# Startracker_Power.net
KiCad netlist of a schematic drawn in Altium Designer
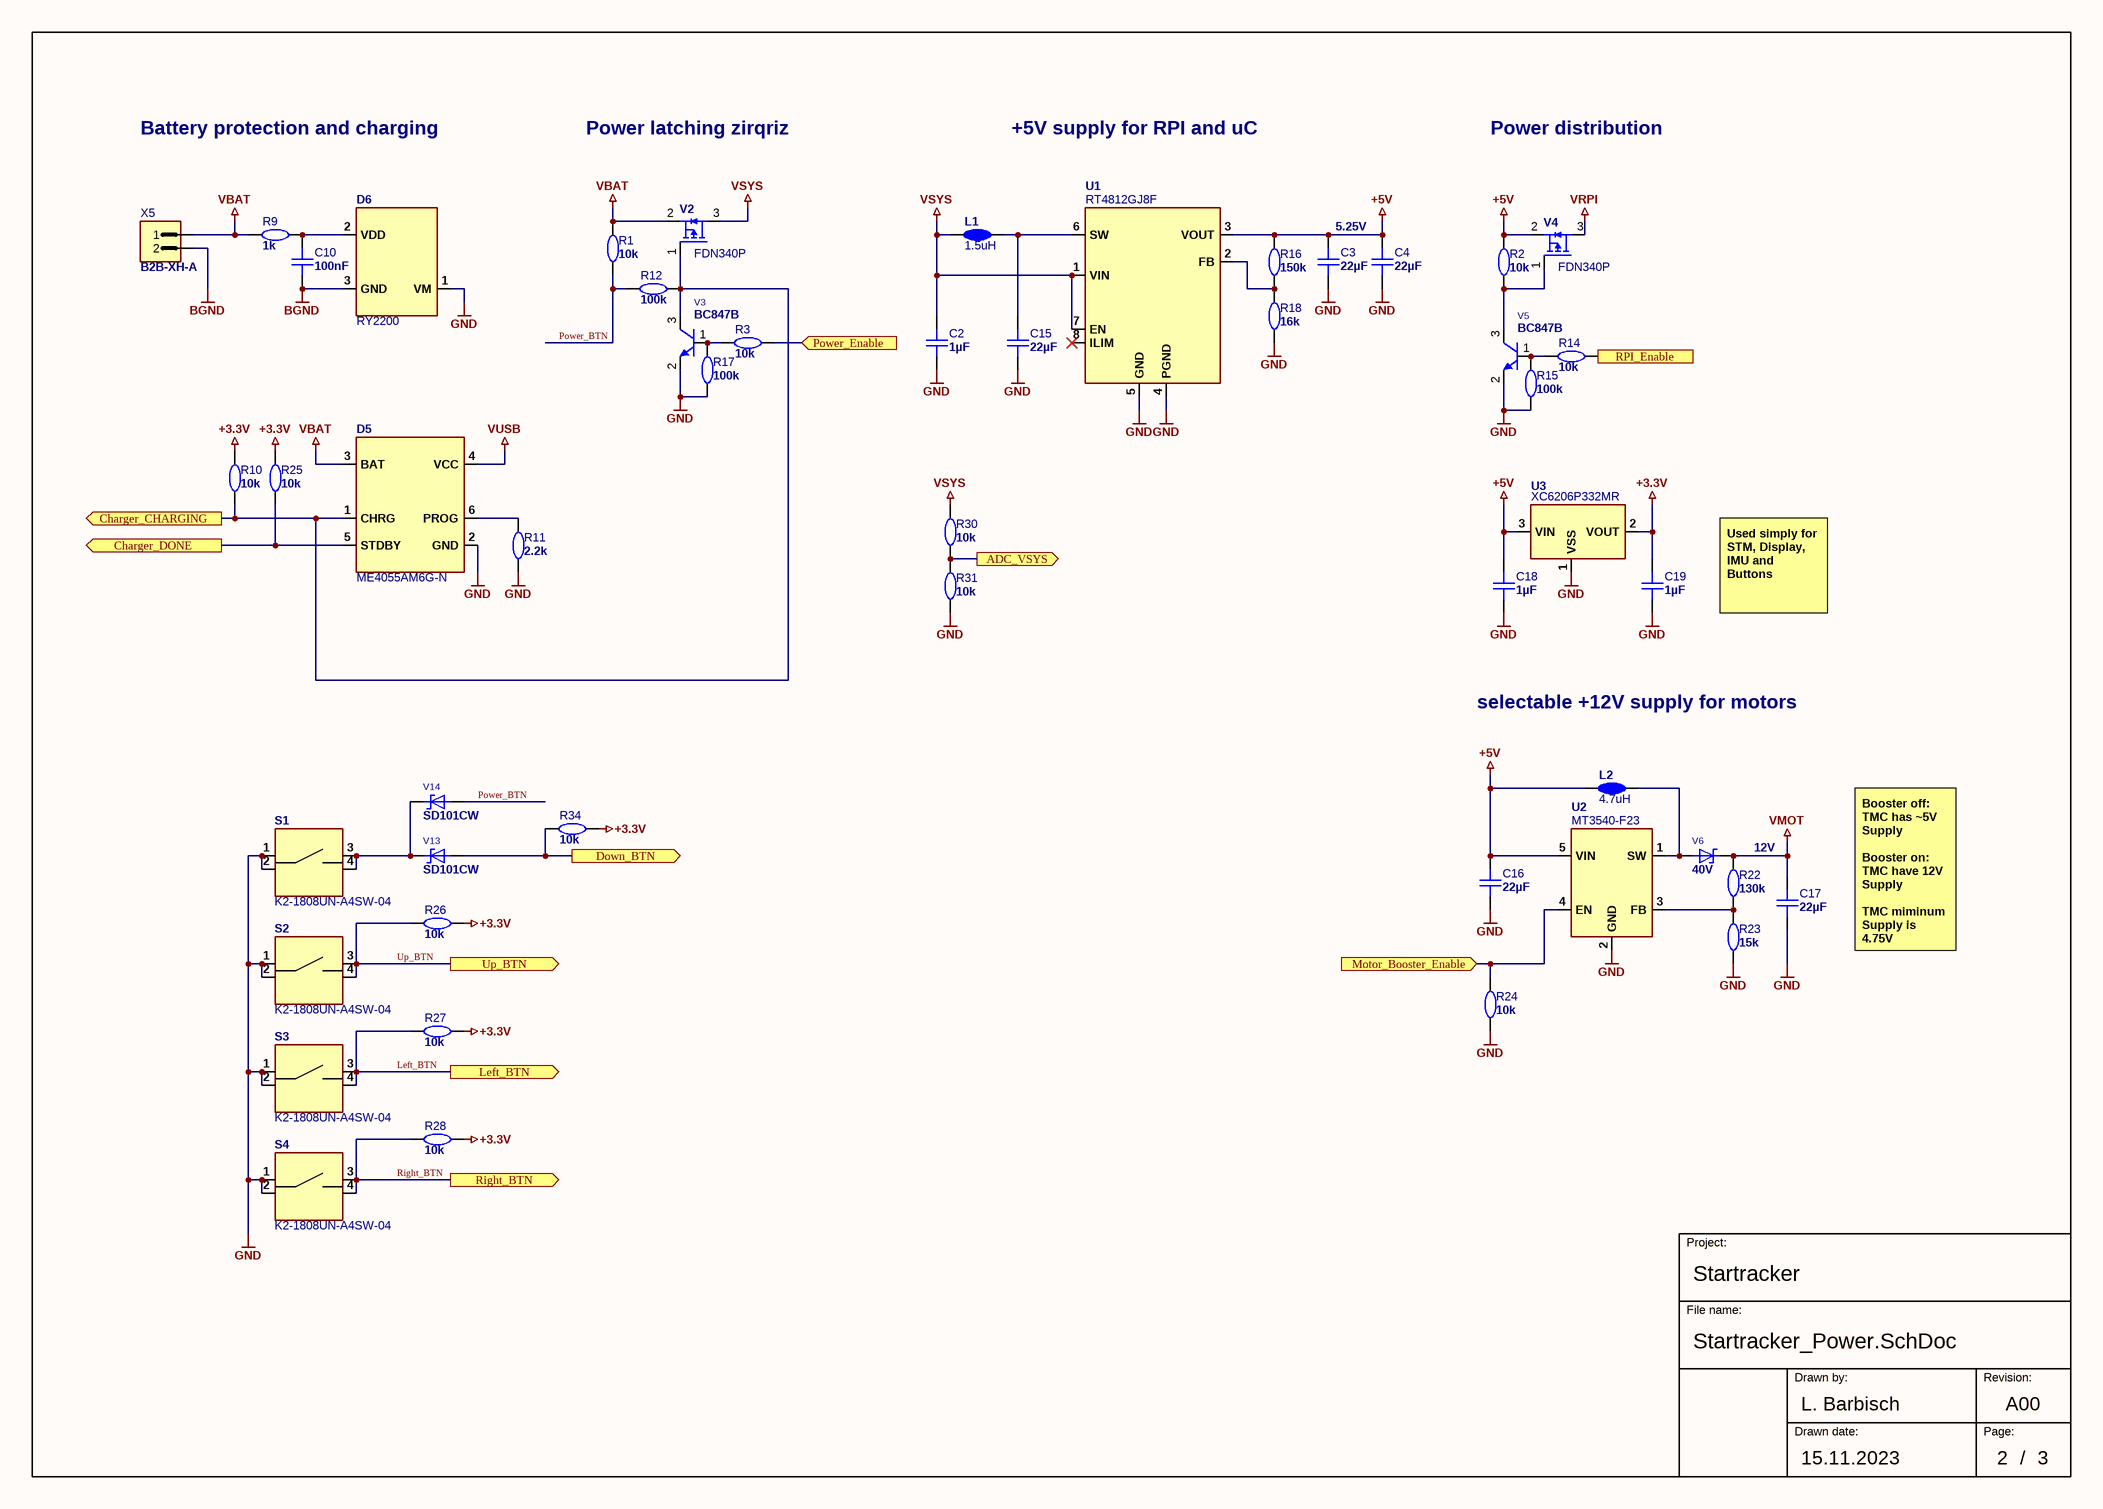
[diagram p0: Startracker_Power.SchDoc]

(export (version "E")
  (design (tool "Eeschema 10.0.6"))
  (components
    (comp (ref "C2")
      (value "1µF")
      (footprint "C-0603_1608_095_L_RF")
      (description "Cap Cer SMD 1u 16V 10% 0603 X7R")
      (fields
        (field (name "MANUFACTURER PART NUMBER") "0603YC105KAT*")
        (field (name "MANUFACTURER") "AVX")
        (field (name "USER") "zupa")
      )
      (libsource (lib "GPV Switzerland SA") (part "CAP"))
    )
    (comp (ref "C3")
      (value "22µF")
      (footprint "C-1206_3216_230_L_RF")
      (description "Cap Cer SMD 22u 25V 10% 1206 X5R")
      (fields
        (field (name "MANUFACTURER PART NUMBER") "GRM31CR61E226KE15*")
        (field (name "MANUFACTURER") "MURATA")
        (field (name "USER") "zupa")
      )
      (libsource (lib "GPV Switzerland SA") (part "CAP"))
    )
    (comp (ref "C4")
      (value "22µF")
      (footprint "C-1206_3216_230_L_RF")
      (description "Cap Cer SMD 22u 25V 10% 1206 X5R")
      (fields
        (field (name "MANUFACTURER PART NUMBER") "GRM31CR61E226KE15*")
        (field (name "MANUFACTURER") "MURATA")
        (field (name "USER") "zupa")
      )
      (libsource (lib "GPV Switzerland SA") (part "CAP"))
    )
    (comp (ref "C10")
      (value "100nF")
      (footprint "C-0603_1608_095_L_RF")
      (description "Cap Cer SMD 100n 50V 10% 0603 X7R")
      (fields
        (field (name "MANUFACTURER") "KEMET")
        (field (name "MANUFACTURER PART NUMBER") "C0603C104K5RAC")
        (field (name "USER") "epph")
      )
      (libsource (lib "GPV Switzerland SA") (part "CAP"))
    )
    (comp (ref "C15")
      (value "22µF")
      (footprint "C-1206_3216_230_L_RF")
      (description "Cap Cer SMD 22u 25V 10% 1206 X5R")
      (fields
        (field (name "MANUFACTURER PART NUMBER") "GRM31CR61E226KE15*")
        (field (name "MANUFACTURER") "MURATA")
        (field (name "USER") "zupa")
      )
      (libsource (lib "GPV Switzerland SA") (part "CAP"))
    )
    (comp (ref "C16")
      (value "22µF")
      (footprint "C-1206_3216_230_L_RF")
      (description "Cap Cer SMD 22u 25V 10% 1206 X5R")
      (fields
        (field (name "MANUFACTURER PART NUMBER") "GRM31CR61E226KE15*")
        (field (name "MANUFACTURER") "MURATA")
        (field (name "USER") "zupa")
      )
      (libsource (lib "GPV Switzerland SA") (part "CAP"))
    )
    (comp (ref "C17")
      (value "22µF")
      (footprint "C-1206_3216_230_L_RF")
      (description "Cap Cer SMD 22u 25V 10% 1206 X5R")
      (fields
        (field (name "MANUFACTURER") "MURATA")
        (field (name "MANUFACTURER PART NUMBER") "GRM31CR61E226KE15*")
        (field (name "USER") "zupa")
      )
      (libsource (lib "GPV Switzerland SA") (part "CAP"))
    )
    (comp (ref "C18")
      (value "1µF")
      (footprint "C-0603_1608_095_L_RF")
      (description "Cap Cer SMD 1u 16V 10% 0603 X7R")
      (fields
        (field (name "MANUFACTURER PART NUMBER") "0603YC105KAT*")
        (field (name "MANUFACTURER") "AVX")
        (field (name "USER") "zupa")
      )
      (libsource (lib "GPV Switzerland SA") (part "CAP"))
    )
    (comp (ref "C19")
      (value "1µF")
      (footprint "C-0603_1608_095_L_RF")
      (description "Cap Cer SMD 1u 16V 10% 0603 X7R")
      (fields
        (field (name "MANUFACTURER PART NUMBER") "0603YC105KAT*")
        (field (name "MANUFACTURER") "AVX")
        (field (name "USER") "zupa")
      )
      (libsource (lib "GPV Switzerland SA") (part "CAP"))
    )
    (comp (ref "D5")
      (value "ME4055AM6G-N")
      (footprint "SOT23-6_N_RF")
      (description "IC Charger Li-Ion 1Cell")
      (fields (field (name "MANUFACTURER") "MICRONE"))
      (libsource (lib "Global Library") (part "ME4055AM6G-N"))
    )
    (comp (ref "D6")
      (value "RY2200")
      (footprint "SOT23_N_RF")
      (description "IC Protection Li-Ion")
      (fields (field (name "MANUFACTURER") "Rychip"))
      (libsource (lib "Global Library") (part "RY2200"))
    )
    (comp (ref "L1")
      (value "1.5uH")
      (footprint "L-0490X0490_N_RF")
      (description "IND 4.7uH 6.4A 4.9x4.9mm")
      (fields
        (field (name "MANUFACTURER") "TAIYO YUDEN")
        (field (name "MANUFACTURER PART NUMBER") "NRS5040T1R5NMGJ")
      )
      (libsource (lib "Global Library") (part "NRS5040T1R5NMGJ"))
    )
    (comp (ref "L2")
      (value "4.7uH")
      (footprint "L-0400X0400_N_RF")
      (description "IND 4.7uH 2.9A 4x4mm")
      (fields
        (field (name "MANUFACTURER") "APV")
        (field (name "MANUFACTURER PART NUMBER") "APSWPA4030S4R7MTF")
      )
      (libsource (lib "Global Library") (part "APSWPA4030S4R7MTF"))
    )
    (comp (ref "R1")
      (value "10k")
      (footprint "R-0603_1608_050_L_RF")
      (description "Res SMD 10k 1% 0.1W 0603")
      (fields
        (field (name "MANUFACTURER") "YAGEO")
        (field (name "MANUFACTURER PART NUMBER") "RC0603FR-0710KL")
        (field (name "USER") "zupa")
      )
      (libsource (lib "GPV Switzerland SA") (part "RES"))
    )
    (comp (ref "R2")
      (value "10k")
      (footprint "R-0603_1608_050_L_RF")
      (description "Res SMD 10k 1% 0.1W 0603")
      (fields
        (field (name "MANUFACTURER") "YAGEO")
        (field (name "MANUFACTURER PART NUMBER") "RC0603FR-0710KL")
        (field (name "USER") "zupa")
      )
      (libsource (lib "GPV Switzerland SA") (part "RES"))
    )
    (comp (ref "R3")
      (value "10k")
      (footprint "R-0603_1608_050_L_RF")
      (description "Res SMD 10k 1% 0.1W 0603")
      (fields
        (field (name "MANUFACTURER") "YAGEO")
        (field (name "MANUFACTURER PART NUMBER") "RC0603FR-0710KL")
        (field (name "USER") "zupa")
      )
      (libsource (lib "GPV Switzerland SA") (part "RES"))
    )
    (comp (ref "R9")
      (value "1k")
      (footprint "R-0603_1608_050_L_RF")
      (description "Res SMD 1k 1% 0.1W 0603")
      (fields
        (field (name "MANUFACTURER") "YAGEO")
        (field (name "MANUFACTURER PART NUMBER") "RC0603FR-071KL")
        (field (name "USER") "zupa")
      )
      (libsource (lib "GPV Switzerland SA") (part "RES"))
    )
    (comp (ref "R10")
      (value "10k")
      (footprint "R-0603_1608_050_L_RF")
      (description "Res SMD 10k 1% 0.1W 0603")
      (fields
        (field (name "MANUFACTURER") "YAGEO")
        (field (name "MANUFACTURER PART NUMBER") "RC0603FR-0710KL")
        (field (name "USER") "zupa")
      )
      (libsource (lib "GPV Switzerland SA") (part "RES"))
    )
    (comp (ref "R11")
      (value "2.2k")
      (footprint "R-0603_1608_050_L_RF")
      (description "Res SMD 2k2 1% 0.1W 0603")
      (fields
        (field (name "MANUFACTURER") "YAGEO")
        (field (name "MANUFACTURER PART NUMBER") "RC0603FR-072K2L")
        (field (name "USER") "zupa")
      )
      (libsource (lib "GPV Switzerland SA") (part "RES"))
    )
    (comp (ref "R12")
      (value "100k")
      (footprint "R-0603_1608_050_L_RF")
      (description "Res SMD 100k 1% 0.1W 0603")
      (fields
        (field (name "MANUFACTURER") "YAGEO")
        (field (name "MANUFACTURER PART NUMBER") "RC0603FR-07100KL")
        (field (name "USER") "napa")
      )
      (libsource (lib "GPV Switzerland SA") (part "RES"))
    )
    (comp (ref "R14")
      (value "10k")
      (footprint "R-0603_1608_050_L_RF")
      (description "Res SMD 10k 1% 0.1W 0603")
      (fields
        (field (name "MANUFACTURER") "YAGEO")
        (field (name "MANUFACTURER PART NUMBER") "RC0603FR-0710KL")
        (field (name "USER") "zupa")
      )
      (libsource (lib "GPV Switzerland SA") (part "RES"))
    )
    (comp (ref "R15")
      (value "100k")
      (footprint "R-0603_1608_050_L_RF")
      (description "Res SMD 100k 1% 0.1W 0603")
      (fields
        (field (name "MANUFACTURER") "YAGEO")
        (field (name "MANUFACTURER PART NUMBER") "RC0603FR-07100KL")
        (field (name "USER") "napa")
      )
      (libsource (lib "GPV Switzerland SA") (part "RES"))
    )
    (comp (ref "R16")
      (value "150k")
      (footprint "R-0603_1608_050_L_RF")
      (description "Res SMD 150k 1% 0.1W 0603")
      (fields
        (field (name "MANUFACTURER") "YAGEO")
        (field (name "MANUFACTURER PART NUMBER") "RC0603FR-07150KL")
        (field (name "USER") "napa")
      )
      (libsource (lib "GPV Switzerland SA") (part "RES"))
    )
    (comp (ref "R17")
      (value "100k")
      (footprint "R-0603_1608_050_L_RF")
      (description "Res SMD 100k 1% 0.1W 0603")
      (fields
        (field (name "MANUFACTURER") "YAGEO")
        (field (name "MANUFACTURER PART NUMBER") "RC0603FR-07100KL")
        (field (name "USER") "napa")
      )
      (libsource (lib "GPV Switzerland SA") (part "RES"))
    )
    (comp (ref "R18")
      (value "16k")
      (footprint "R-0603_1608_050_L_RF")
      (description "Res SMD 16k 1% 0.1W 0603")
      (fields
        (field (name "MANUFACTURER") "YAGEO")
        (field (name "MANUFACTURER PART NUMBER") "RC0603FR-0716KL")
        (field (name "USER") "napa")
      )
      (libsource (lib "GPV Switzerland SA") (part "RES"))
    )
    (comp (ref "R22")
      (value "130k")
      (footprint "R-0603_1608_050_L_RF")
      (description "Res SMD 130k 1% 0.1W 0603")
      (fields
        (field (name "MANUFACTURER PART NUMBER") "RT0603FRE07130KL")
        (field (name "MANUFACTURER") "YAGEO")
        (field (name "USER") "napa")
      )
      (libsource (lib "GPV Switzerland SA") (part "RES"))
    )
    (comp (ref "R23")
      (value "15k")
      (footprint "R-0603_1608_050_L_RF")
      (description "Res SMD 15k 1% 0.1W 0603")
      (fields
        (field (name "MANUFACTURER") "YAGEO")
        (field (name "MANUFACTURER PART NUMBER") "RC0603FR-0715KL")
        (field (name "USER") "zupa")
      )
      (libsource (lib "GPV Switzerland SA") (part "RES"))
    )
    (comp (ref "R24")
      (value "10k")
      (footprint "R-0603_1608_050_L_RF")
      (description "Res SMD 10k 1% 0.1W 0603")
      (fields
        (field (name "MANUFACTURER") "YAGEO")
        (field (name "MANUFACTURER PART NUMBER") "RC0603FR-0710KL")
        (field (name "USER") "zupa")
      )
      (libsource (lib "GPV Switzerland SA") (part "RES"))
    )
    (comp (ref "R25")
      (value "10k")
      (footprint "R-0603_1608_050_L_RF")
      (description "Res SMD 10k 1% 0.1W 0603")
      (fields
        (field (name "MANUFACTURER") "YAGEO")
        (field (name "MANUFACTURER PART NUMBER") "RC0603FR-0710KL")
        (field (name "USER") "zupa")
      )
      (libsource (lib "GPV Switzerland SA") (part "RES"))
    )
    (comp (ref "R26")
      (value "10k")
      (footprint "R-0603_1608_050_L_RF")
      (description "Res SMD 10k 1% 0.1W 0603")
      (fields
        (field (name "MANUFACTURER") "YAGEO")
        (field (name "MANUFACTURER PART NUMBER") "RC0603FR-0710KL")
        (field (name "USER") "zupa")
      )
      (libsource (lib "GPV Switzerland SA") (part "RES"))
    )
    (comp (ref "R27")
      (value "10k")
      (footprint "R-0603_1608_050_L_RF")
      (description "Res SMD 10k 1% 0.1W 0603")
      (fields
        (field (name "MANUFACTURER") "YAGEO")
        (field (name "MANUFACTURER PART NUMBER") "RC0603FR-0710KL")
        (field (name "USER") "zupa")
      )
      (libsource (lib "GPV Switzerland SA") (part "RES"))
    )
    (comp (ref "R28")
      (value "10k")
      (footprint "R-0603_1608_050_L_RF")
      (description "Res SMD 10k 1% 0.1W 0603")
      (fields
        (field (name "MANUFACTURER") "YAGEO")
        (field (name "MANUFACTURER PART NUMBER") "RC0603FR-0710KL")
        (field (name "USER") "zupa")
      )
      (libsource (lib "GPV Switzerland SA") (part "RES"))
    )
    (comp (ref "R30")
      (value "10k")
      (footprint "R-0603_1608_050_L_RF")
      (description "Res SMD 10k 1% 0.1W 0603")
      (fields
        (field (name "MANUFACTURER") "YAGEO")
        (field (name "MANUFACTURER PART NUMBER") "RC0603FR-0710KL")
        (field (name "USER") "zupa")
      )
      (libsource (lib "GPV Switzerland SA") (part "RES"))
    )
    (comp (ref "R31")
      (value "10k")
      (footprint "R-0603_1608_050_L_RF")
      (description "Res SMD 10k 1% 0.1W 0603")
      (fields
        (field (name "MANUFACTURER") "YAGEO")
        (field (name "MANUFACTURER PART NUMBER") "RC0603FR-0710KL")
        (field (name "USER") "zupa")
      )
      (libsource (lib "GPV Switzerland SA") (part "RES"))
    )
    (comp (ref "R34")
      (value "10k")
      (footprint "R-0603_1608_050_L_RF")
      (description "Res SMD 10k 1% 0.1W 0603")
      (fields
        (field (name "MANUFACTURER") "YAGEO")
        (field (name "MANUFACTURER PART NUMBER") "RC0603FR-0710KL")
        (field (name "USER") "zupa")
      )
      (libsource (lib "GPV Switzerland SA") (part "RES"))
    )
    (comp (ref "S1")
      (value "K2-1808UN-A4SW-04")
      (footprint "K2-1808UN-A4SW-04")
      (description "BUTTON tactile 12V 50mA")
      (fields (field (name "MANUFACTURER") "HROparts"))
      (libsource (lib "Global Library") (part "K2-1808UN-A4SW-04"))
    )
    (comp (ref "S2")
      (value "K2-1808UN-A4SW-04")
      (footprint "K2-1808UN-A4SW-04")
      (description "BUTTON tactile 12V 50mA")
      (fields (field (name "MANUFACTURER") "HROparts"))
      (libsource (lib "Global Library") (part "K2-1808UN-A4SW-04"))
    )
    (comp (ref "S3")
      (value "K2-1808UN-A4SW-04")
      (footprint "K2-1808UN-A4SW-04")
      (description "BUTTON tactile 12V 50mA")
      (fields (field (name "MANUFACTURER") "HROparts"))
      (libsource (lib "Global Library") (part "K2-1808UN-A4SW-04"))
    )
    (comp (ref "S4")
      (value "K2-1808UN-A4SW-04")
      (footprint "K2-1808UN-A4SW-04")
      (description "BUTTON tactile 12V 50mA")
      (fields (field (name "MANUFACTURER") "HROparts"))
      (libsource (lib "Global Library") (part "K2-1808UN-A4SW-04"))
    )
    (comp (ref "U1")
      (value "RT4812GJ8F")
      (footprint "TSOT-23-8")
      (description "IC Boost Converter 1.8V-5.5V to 1.8-5.5V 2.1A")
      (fields (field (name "MANUFACTURER") "Richtek"))
      (libsource (lib "Global Library") (part "RT4812GJ8F"))
    )
    (comp (ref "U2")
      (value "MT3540-F23")
      (footprint "SOT23-5_N_RF")
      (description "IC Boost Converter 2.5V-5.5V upto 28V 1.5A")
      (fields (field (name "MANUFACTURER") "Aerosemi"))
      (libsource (lib "Global Library") (part "MT3540-F23"))
    )
    (comp (ref "U3")
      (value "XC6206P332MR")
      (footprint "SOT23_N_RF")
      (description "IC REG LDO 3.3V 200mA")
      (fields (field (name "MANUFACTURER") "Torex"))
      (libsource (lib "Global Library") (part "XC6206P332MR"))
    )
    (comp (ref "V2")
      (value "FDN340P")
      (footprint "SOT23_N_RF")
      (description "MOSFET PCH -2A 20V")
      (fields (field (name "MANUFACTURER") "onsemi"))
      (libsource (lib "Global Library") (part "FDN340P"))
    )
    (comp (ref "V3")
      (value "BC847B")
      (footprint "SOT23_L_RF")
      (description "TRANS SMD NPN 45V 0.1A BC847B SOT23")
      (fields
        (field (name "MANUFACTURER") "NXP Semiconductors")
        (field (name "MANUFACTURER PART NUMBER") "BC847B/C")
        (field (name "USER") "zupa")
      )
      (libsource (lib "GPV Switzerland SA") (part "BIPO-NPN_B1-C3-E2"))
    )
    (comp (ref "V4")
      (value "FDN340P")
      (footprint "SOT23_N_RF")
      (description "MOSFET PCH -2A 20V")
      (fields (field (name "MANUFACTURER") "onsemi"))
      (libsource (lib "Global Library") (part "FDN340P"))
    )
    (comp (ref "V5")
      (value "BC847B")
      (footprint "SOT23_L_RF")
      (description "TRANS SMD NPN 45V 0.1A BC847B SOT23")
      (fields
        (field (name "MANUFACTURER") "NXP Semiconductors")
        (field (name "MANUFACTURER PART NUMBER") "BC847B/C")
        (field (name "USER") "zupa")
      )
      (libsource (lib "GPV Switzerland SA") (part "BIPO-NPN_B1-C3-E2"))
    )
    (comp (ref "V6")
      (value "40V")
      (footprint "SMA_DO214AC_L_RF")
      (description "Diode Schottky 40V 1A SMA")
      (fields
        (field (name "MANUFACTURER") "VISHAY")
        (field (name "MANUFACTURER PART NUMBER") "SS14-E3")
        (field (name "USER") "epph")
      )
      (libsource (lib "GPV Switzerland SA") (part "SCHOTTKY"))
    )
    (comp (ref "V13")
      (value "SD101CW")
      (footprint "SOD123_L_RF")
      (description "Diode Schottky  1mA 40 Volt")
      (fields
        (field (name "MANUFACTURER PART NUMBER") "SD101CW-E3-08")
        (field (name "MANUFACTURER") "VISHAY")
        (field (name "USER") "zupa")
      )
      (libsource (lib "GPV Switzerland SA") (part "SCHOTTKY"))
    )
    (comp (ref "V14")
      (value "SD101CW")
      (footprint "SOD123_L_RF")
      (description "Diode Schottky  1mA 40 Volt")
      (fields
        (field (name "MANUFACTURER PART NUMBER") "SD101CW-E3-08")
        (field (name "MANUFACTURER") "VISHAY")
        (field (name "USER") "zupa")
      )
      (libsource (lib "GPV Switzerland SA") (part "SCHOTTKY"))
    )
    (comp (ref "X5")
      (value "B2B-XH-A")
      (footprint "X-0074X0057-R_M02_P0250_JST_B2B-XH-A")
      (description "CONN HEADER  2POS_JST_B2B-XH")
      (fields
        (field (name "MANUFACTURER") "JST")
        (field (name "Comment") "CONN HEADER XH 2POS THT")
        (field (name "USER") "balu")
      )
      (libsource (lib "GPV Switzerland SA") (part "Connector-2P"))
    )
  )
  (nets
    (net (code "1") (name "+3.3V") (class "Default")
      (node (ref "C19") (pin "2") (pinfunction "2_2") (pintype "passive"))
      (node (ref "R10") (pin "2") (pinfunction "2_2") (pintype "passive"))
      (node (ref "R25") (pin "2") (pinfunction "2_2") (pintype "passive"))
      (node (ref "R26") (pin "2") (pinfunction "2_2") (pintype "passive"))
      (node (ref "R27") (pin "2") (pinfunction "2_2") (pintype "passive"))
      (node (ref "R28") (pin "2") (pinfunction "2_2") (pintype "passive"))
      (node (ref "R34") (pin "2") (pinfunction "2_2") (pintype "passive"))
      (node (ref "U3") (pin "2") (pinfunction "VOUT_2") (pintype "passive"))
    )
    (net (code "2") (name "+5V") (class "Default")
      (node (ref "C16") (pin "2") (pinfunction "2_2") (pintype "passive"))
      (node (ref "C18") (pin "2") (pinfunction "2_2") (pintype "passive"))
      (node (ref "C3") (pin "2") (pinfunction "2_2") (pintype "passive"))
      (node (ref "C4") (pin "2") (pinfunction "2_2") (pintype "passive"))
      (node (ref "L2") (pin "1") (pinfunction "1_1") (pintype "passive"))
      (node (ref "R16") (pin "2") (pinfunction "2_2") (pintype "passive"))
      (node (ref "R2") (pin "2") (pinfunction "2_2") (pintype "passive"))
      (node (ref "U1") (pin "3") (pinfunction "VOUT_3") (pintype "passive"))
      (node (ref "U2") (pin "5") (pinfunction "VIN_5") (pintype "passive"))
      (node (ref "U3") (pin "3") (pinfunction "VIN_3") (pintype "passive"))
      (node (ref "V4") (pin "2") (pinfunction "S_2") (pintype "passive"))
    )
    (net (code "3") (name "/ADC_VSYS") (class "Default")
      (node (ref "R30") (pin "1") (pinfunction "1_1") (pintype "passive"))
      (node (ref "R31") (pin "2") (pinfunction "2_2") (pintype "passive"))
    )
    (net (code "4") (name "/Charger_CHARGING") (class "Default")
      (node (ref "D5") (pin "1") (pinfunction "CHRG_1") (pintype "passive"))
      (node (ref "R10") (pin "1") (pinfunction "1_1") (pintype "passive"))
      (node (ref "R12") (pin "1") (pinfunction "1_1") (pintype "passive"))
      (node (ref "V2") (pin "1") (pinfunction "G_1") (pintype "passive"))
      (node (ref "V3") (pin "3") (pinfunction "C_3") (pintype "passive"))
    )
    (net (code "5") (name "/Charger_DONE") (class "Default")
      (node (ref "D5") (pin "5") (pinfunction "STDBY_5") (pintype "passive"))
      (node (ref "R25") (pin "1") (pinfunction "1_1") (pintype "passive"))
    )
    (net (code "6") (name "/Down_BTN") (class "Default")
      (node (ref "R34") (pin "1") (pinfunction "1_1") (pintype "passive"))
      (node (ref "V13") (pin "1") (pinfunction "1_1") (pintype "passive"))
    )
    (net (code "7") (name "/Left_BTN") (class "Default")
      (node (ref "R27") (pin "1") (pinfunction "1_1") (pintype "passive"))
      (node (ref "S3") (pin "3") (pintype "passive"))
      (node (ref "S3") (pin "4") (pintype "passive"))
    )
    (net (code "8") (name "/Motor_Booster_Enable") (class "Default")
      (node (ref "R24") (pin "1") (pinfunction "1_1") (pintype "passive"))
      (node (ref "U2") (pin "4") (pinfunction "EN_4") (pintype "passive"))
    )
    (net (code "9") (name "/Power_BTN") (class "Default")
      (node (ref "R1") (pin "1") (pinfunction "1_1") (pintype "passive"))
      (node (ref "R12") (pin "2") (pinfunction "2_2") (pintype "passive"))
      (node (ref "V14") (pin "1") (pinfunction "1_1") (pintype "passive"))
    )
    (net (code "10") (name "/Power_Enable") (class "Default")
      (node (ref "R3") (pin "2") (pinfunction "2_2") (pintype "passive"))
    )
    (net (code "11") (name "/RPI_Enable") (class "Default")
      (node (ref "R14") (pin "2") (pinfunction "2_2") (pintype "passive"))
    )
    (net (code "12") (name "/Right_BTN") (class "Default")
      (node (ref "R28") (pin "1") (pinfunction "1_1") (pintype "passive"))
      (node (ref "S4") (pin "3") (pintype "passive"))
      (node (ref "S4") (pin "4") (pintype "passive"))
    )
    (net (code "13") (name "/Up_BTN") (class "Default")
      (node (ref "R26") (pin "1") (pinfunction "1_1") (pintype "passive"))
      (node (ref "S2") (pin "3") (pintype "passive"))
      (node (ref "S2") (pin "4") (pintype "passive"))
    )
    (net (code "14") (name "BGND") (class "Default")
      (node (ref "C10") (pin "1") (pinfunction "1_1") (pintype "passive"))
      (node (ref "D6") (pin "3") (pinfunction "GND_3") (pintype "passive"))
      (node (ref "X5") (pin "2") (pinfunction "2_2") (pintype "passive"))
    )
    (net (code "15") (name "GND") (class "Default")
      (node (ref "C15") (pin "1") (pinfunction "1_1") (pintype "passive"))
      (node (ref "C16") (pin "1") (pinfunction "1_1") (pintype "passive"))
      (node (ref "C17") (pin "1") (pinfunction "1_1") (pintype "passive"))
      (node (ref "C18") (pin "1") (pinfunction "1_1") (pintype "passive"))
      (node (ref "C19") (pin "1") (pinfunction "1_1") (pintype "passive"))
      (node (ref "C2") (pin "1") (pinfunction "1_1") (pintype "passive"))
      (node (ref "C3") (pin "1") (pinfunction "1_1") (pintype "passive"))
      (node (ref "C4") (pin "1") (pinfunction "1_1") (pintype "passive"))
      (node (ref "D5") (pin "2") (pinfunction "GND_2") (pintype "passive"))
      (node (ref "D6") (pin "1") (pinfunction "VM_1") (pintype "passive"))
      (node (ref "R11") (pin "1") (pinfunction "1_1") (pintype "passive"))
      (node (ref "R15") (pin "1") (pinfunction "1_1") (pintype "passive"))
      (node (ref "R17") (pin "1") (pinfunction "1_1") (pintype "passive"))
      (node (ref "R18") (pin "1") (pinfunction "1_1") (pintype "passive"))
      (node (ref "R23") (pin "1") (pinfunction "1_1") (pintype "passive"))
      (node (ref "R24") (pin "2") (pinfunction "2_2") (pintype "passive"))
      (node (ref "R31") (pin "1") (pinfunction "1_1") (pintype "passive"))
      (node (ref "S1") (pin "1") (pintype "passive"))
      (node (ref "S1") (pin "2") (pintype "passive"))
      (node (ref "S2") (pin "1") (pintype "passive"))
      (node (ref "S2") (pin "2") (pintype "passive"))
      (node (ref "S3") (pin "1") (pintype "passive"))
      (node (ref "S3") (pin "2") (pintype "passive"))
      (node (ref "S4") (pin "1") (pintype "passive"))
      (node (ref "S4") (pin "2") (pintype "passive"))
      (node (ref "U1") (pin "4") (pinfunction "PGND_4") (pintype "passive"))
      (node (ref "U1") (pin "5") (pinfunction "GND_5") (pintype "passive"))
      (node (ref "U2") (pin "2") (pinfunction "GND_2") (pintype "passive"))
      (node (ref "U3") (pin "1") (pinfunction "VSS_1") (pintype "passive"))
      (node (ref "V3") (pin "2") (pinfunction "E_2") (pintype "passive"))
      (node (ref "V5") (pin "2") (pinfunction "E_2") (pintype "passive"))
    )
    (net (code "16") (name "Net-(D5-PROG)") (class "Default")
      (node (ref "D5") (pin "6") (pinfunction "PROG_6") (pintype "passive"))
      (node (ref "R11") (pin "2") (pinfunction "2_2") (pintype "passive"))
    )
    (net (code "17") (name "Net-(D6-VDD)") (class "Default")
      (node (ref "C10") (pin "2") (pinfunction "2_2") (pintype "passive"))
      (node (ref "D6") (pin "2") (pinfunction "VDD_2") (pintype "passive"))
      (node (ref "R9") (pin "2") (pinfunction "2_2") (pintype "passive"))
    )
    (net (code "18") (name "Net-(S1-Pad3)") (class "Default")
      (node (ref "S1") (pin "3") (pintype "passive"))
      (node (ref "S1") (pin "4") (pintype "passive"))
      (node (ref "V13") (pin "2") (pinfunction "2_2") (pintype "passive"))
      (node (ref "V14") (pin "2") (pinfunction "2_2") (pintype "passive"))
    )
    (net (code "19") (name "Net-(U1-FB)") (class "Default")
      (node (ref "R16") (pin "1") (pinfunction "1_1") (pintype "passive"))
      (node (ref "R18") (pin "2") (pinfunction "2_2") (pintype "passive"))
      (node (ref "U1") (pin "2") (pinfunction "FB_2") (pintype "passive"))
    )
    (net (code "20") (name "Net-(U1-SW)") (class "Default")
      (node (ref "C15") (pin "2") (pinfunction "2_2") (pintype "passive"))
      (node (ref "L1") (pin "2") (pinfunction "2_2") (pintype "passive"))
      (node (ref "U1") (pin "6") (pinfunction "SW_6") (pintype "passive"))
    )
    (net (code "21") (name "Net-(U2-FB)") (class "Default")
      (node (ref "R22") (pin "1") (pinfunction "1_1") (pintype "passive"))
      (node (ref "R23") (pin "2") (pinfunction "2_2") (pintype "passive"))
      (node (ref "U2") (pin "3") (pinfunction "FB_3") (pintype "passive"))
    )
    (net (code "22") (name "Net-(U2-SW)") (class "Default")
      (node (ref "L2") (pin "2") (pinfunction "2_2") (pintype "passive"))
      (node (ref "U2") (pin "1") (pinfunction "SW_1") (pintype "passive"))
      (node (ref "V6") (pin "1") (pinfunction "1_1") (pintype "passive"))
    )
    (net (code "23") (name "Net-(V3-B)") (class "Default")
      (node (ref "R17") (pin "2") (pinfunction "2_2") (pintype "passive"))
      (node (ref "R3") (pin "1") (pinfunction "1_1") (pintype "passive"))
      (node (ref "V3") (pin "1") (pinfunction "B_1") (pintype "passive"))
    )
    (net (code "24") (name "Net-(V4-G)") (class "Default")
      (node (ref "R2") (pin "1") (pinfunction "1_1") (pintype "passive"))
      (node (ref "V4") (pin "1") (pinfunction "G_1") (pintype "passive"))
      (node (ref "V5") (pin "3") (pinfunction "C_3") (pintype "passive"))
    )
    (net (code "25") (name "Net-(V5-B)") (class "Default")
      (node (ref "R14") (pin "1") (pinfunction "1_1") (pintype "passive"))
      (node (ref "R15") (pin "2") (pinfunction "2_2") (pintype "passive"))
      (node (ref "V5") (pin "1") (pinfunction "B_1") (pintype "passive"))
    )
    (net (code "26") (name "VBAT") (class "Default")
      (node (ref "D5") (pin "3") (pinfunction "BAT_3") (pintype "passive"))
      (node (ref "R1") (pin "2") (pinfunction "2_2") (pintype "passive"))
      (node (ref "R9") (pin "1") (pinfunction "1_1") (pintype "passive"))
      (node (ref "V2") (pin "2") (pinfunction "S_2") (pintype "passive"))
      (node (ref "X5") (pin "1") (pinfunction "1_1") (pintype "passive"))
    )
    (net (code "27") (name "VMOT") (class "Default")
      (node (ref "C17") (pin "2") (pinfunction "2_2") (pintype "passive"))
      (node (ref "R22") (pin "2") (pinfunction "2_2") (pintype "passive"))
      (node (ref "V6") (pin "2") (pinfunction "2_2") (pintype "passive"))
    )
    (net (code "28") (name "VRPI") (class "Default")
      (node (ref "V4") (pin "3") (pinfunction "D_3") (pintype "passive"))
    )
    (net (code "29") (name "VSYS") (class "Default")
      (node (ref "C2") (pin "2") (pinfunction "2_2") (pintype "passive"))
      (node (ref "L1") (pin "1") (pinfunction "1_1") (pintype "passive"))
      (node (ref "R30") (pin "2") (pinfunction "2_2") (pintype "passive"))
      (node (ref "U1") (pin "1") (pinfunction "VIN_1") (pintype "passive"))
      (node (ref "U1") (pin "7") (pinfunction "EN_7") (pintype "passive"))
      (node (ref "V2") (pin "3") (pinfunction "D_3") (pintype "passive"))
    )
    (net (code "30") (name "VUSB") (class "Default")
      (node (ref "D5") (pin "4") (pinfunction "VCC_4") (pintype "passive"))
    )
    (net (code "31") (name "unconnected-(U1-ILIM-Pad8)") (class "Default")
      (node (ref "U1") (pin "8") (pinfunction "ILIM_8") (pintype "passive+no_connect"))
    )
  )
)
